# mplex_v2.net
KiCad netlist of a schematic drawn in EAGLE
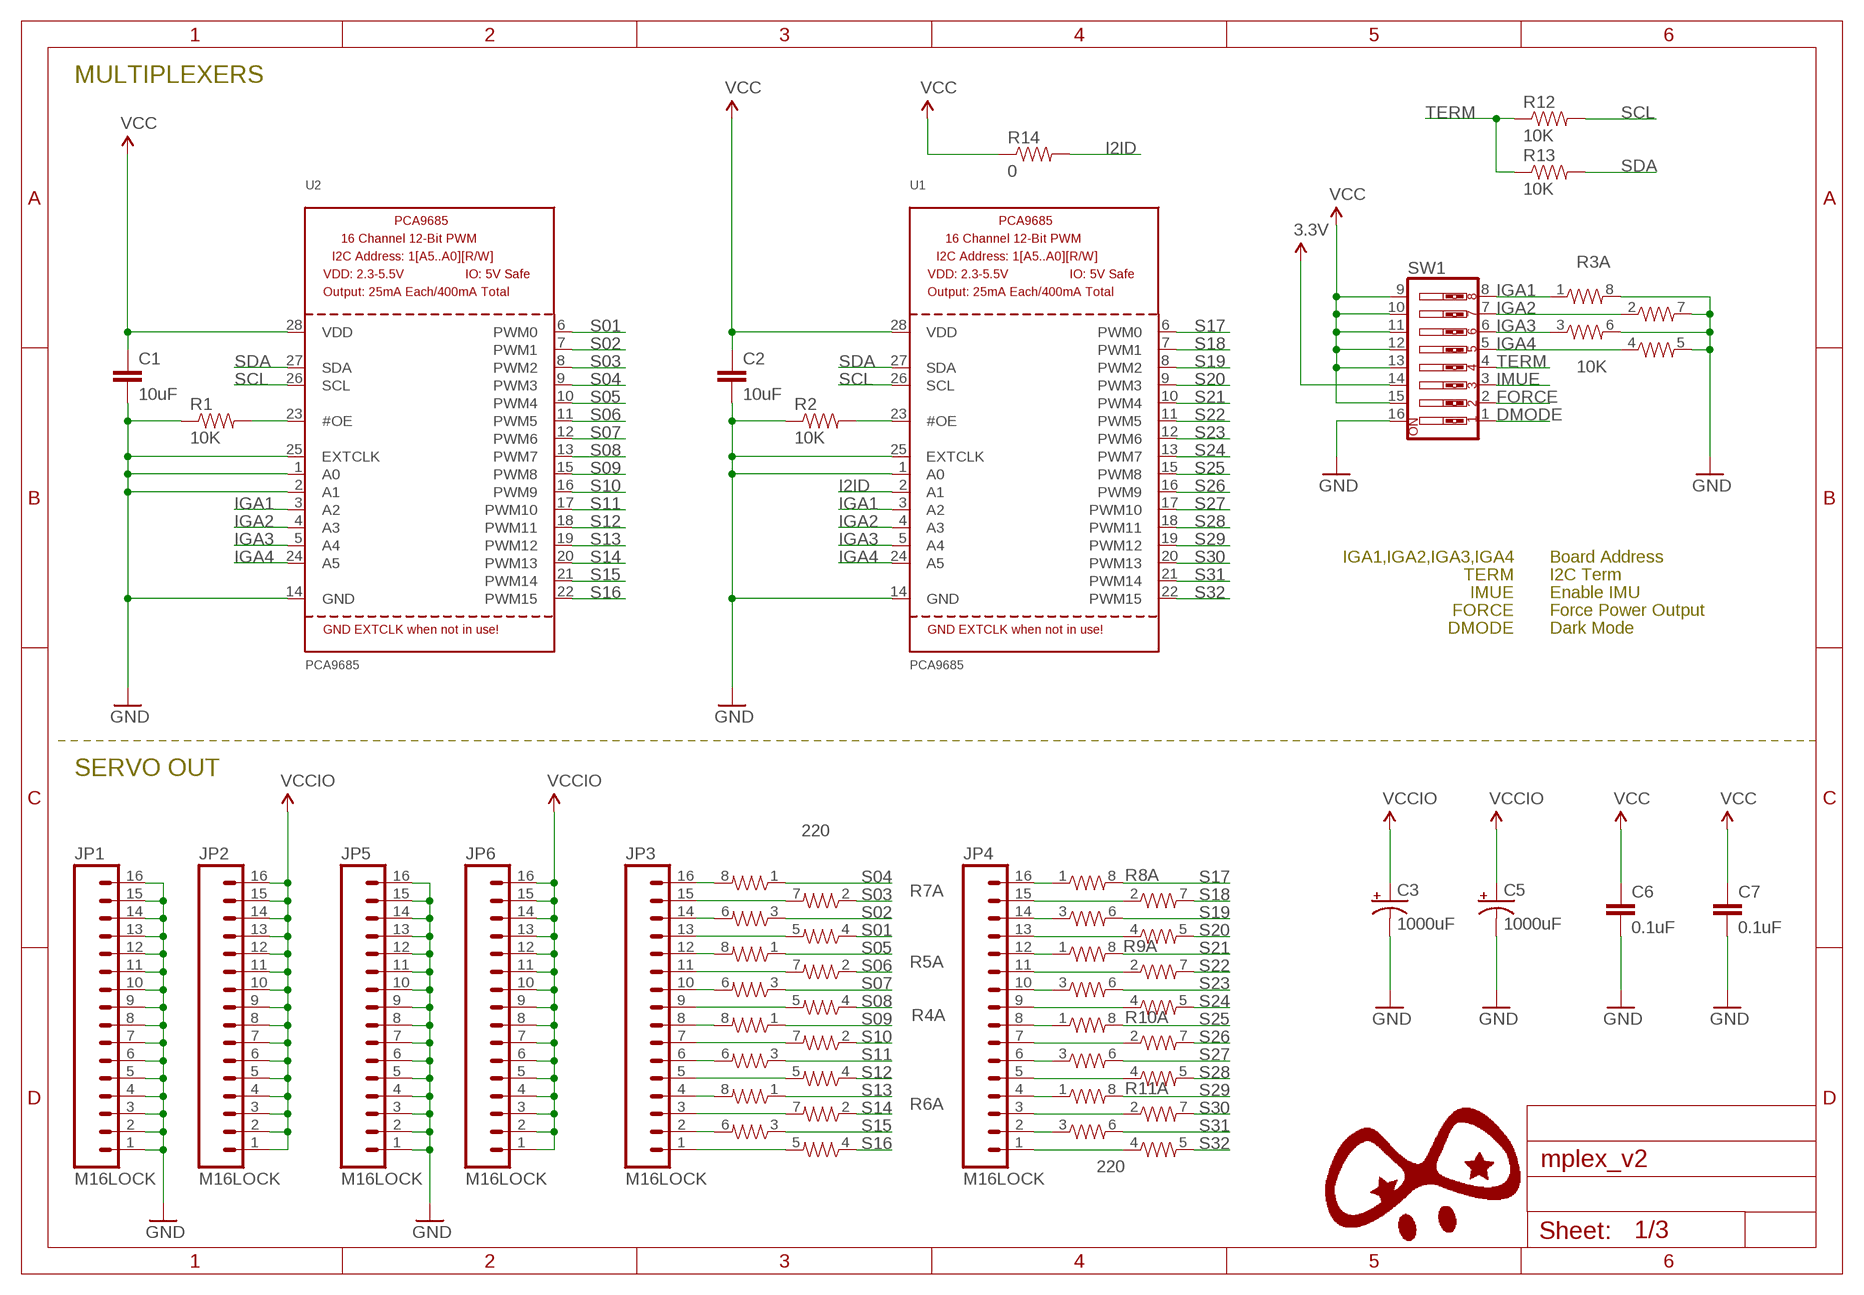
[diagram p0: schematic, sheet 1]
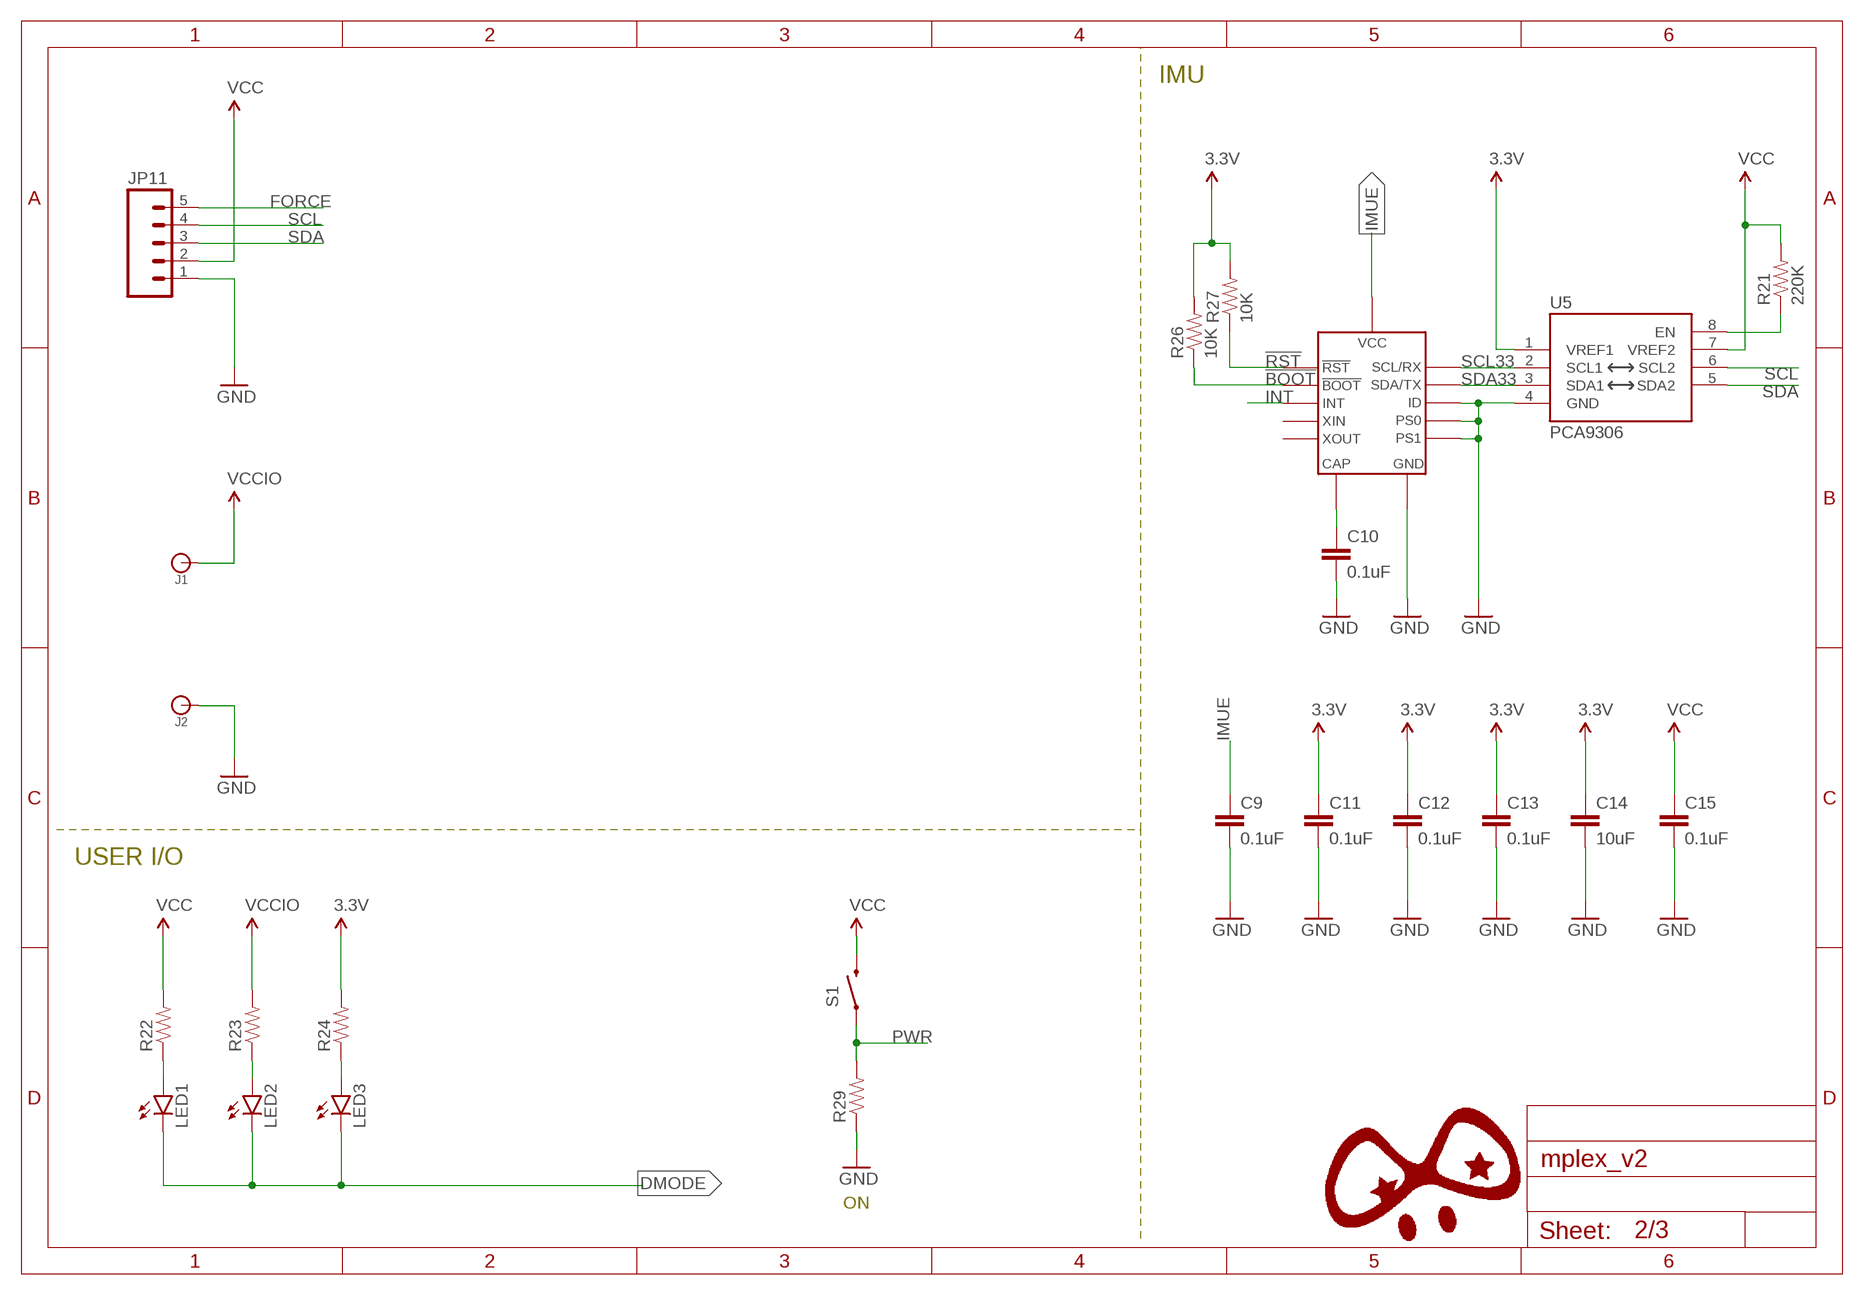
[diagram p1: schematic, sheet 2]
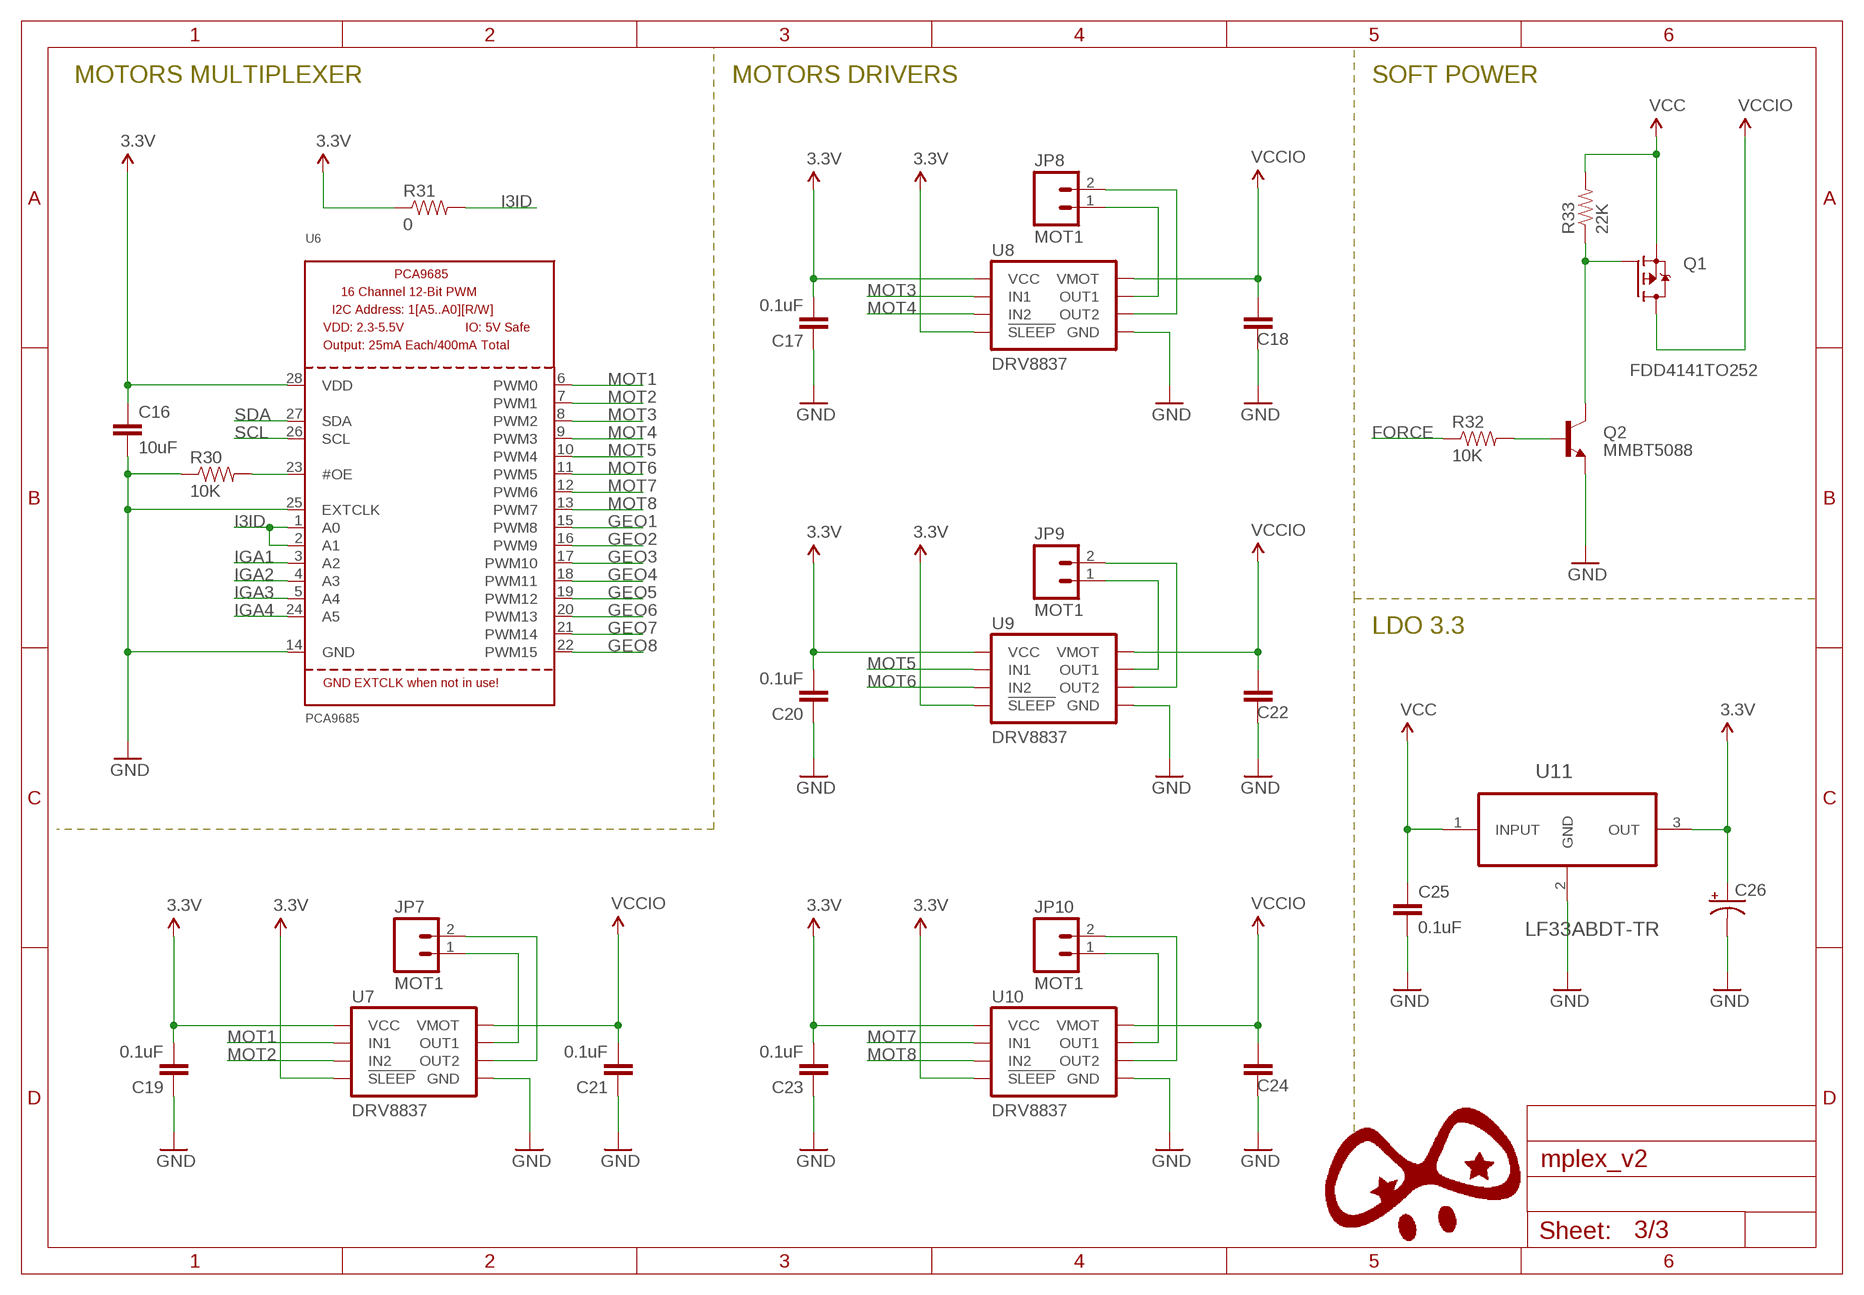
[diagram p2: schematic, sheet 3]

(export (version "E")
  (design (tool "Eeschema 10.0.6"))
  (components
    (comp (ref "C16")
      (value "10uF")
      (footprint "eagle-import:0603-CAP")
      (libsource (lib "eagle-import") (part "10UF-6.3V-20%(0603)"))
    )
    (comp (ref "C17")
      (value "0.1uF")
      (footprint "eagle-import:0603-CAP")
      (libsource (lib "eagle-import") (part "SparkFun-Passives_CAP0603-CAP"))
    )
    (comp (ref "C18")
      (value "0.1uF")
      (footprint "eagle-import:0603-CAP")
      (libsource (lib "eagle-import") (part "SparkFun-Passives_CAP0603-CAP"))
    )
    (comp (ref "C19")
      (value "0.1uF")
      (footprint "eagle-import:0603-CAP")
      (libsource (lib "eagle-import") (part "SparkFun-Passives_CAP0603-CAP"))
    )
    (comp (ref "C20")
      (value "0.1uF")
      (footprint "eagle-import:0603-CAP")
      (libsource (lib "eagle-import") (part "SparkFun-Passives_CAP0603-CAP"))
    )
    (comp (ref "C21")
      (value "0.1uF")
      (footprint "eagle-import:0603-CAP")
      (libsource (lib "eagle-import") (part "SparkFun-Passives_CAP0603-CAP"))
    )
    (comp (ref "C22")
      (value "0.1uF")
      (footprint "eagle-import:0603-CAP")
      (libsource (lib "eagle-import") (part "SparkFun-Passives_CAP0603-CAP"))
    )
    (comp (ref "C23")
      (value "0.1uF")
      (footprint "eagle-import:0603-CAP")
      (libsource (lib "eagle-import") (part "SparkFun-Passives_CAP0603-CAP"))
    )
    (comp (ref "C24")
      (value "0.1uF")
      (footprint "eagle-import:0603-CAP")
      (libsource (lib "eagle-import") (part "SparkFun-Passives_CAP0603-CAP"))
    )
    (comp (ref "C25")
      (value "0.1uF")
      (footprint "eagle-import:1210")
      (libsource (lib "eagle-import") (part "CAP1210"))
    )
    (comp (ref "C26")
      (value "CAP_POLD")
      (footprint "eagle-import:PANASONIC_D")
      (libsource (lib "eagle-import") (part "CAP_POLD"))
    )
    (comp (ref "JP7")
      (value "MOT1")
      (footprint "eagle-import:MOLEX-1X2")
      (libsource (lib "eagle-import") (part "M02POLAR"))
    )
    (comp (ref "JP8")
      (value "MOT1")
      (footprint "eagle-import:MOLEX-1X2")
      (libsource (lib "eagle-import") (part "M02POLAR"))
    )
    (comp (ref "JP9")
      (value "MOT1")
      (footprint "eagle-import:MOLEX-1X2")
      (libsource (lib "eagle-import") (part "M02POLAR"))
    )
    (comp (ref "JP10")
      (value "MOT1")
      (footprint "eagle-import:MOLEX-1X2")
      (libsource (lib "eagle-import") (part "M02POLAR"))
    )
    (comp (ref "Q1")
      (value "FDD4141TO252")
      (footprint "eagle-import:TO252")
      (libsource (lib "eagle-import") (part "FDD4141TO252"))
    )
    (comp (ref "Q2")
      (value "MMBT5088")
      (footprint "eagle-import:SOT23-3")
      (libsource (lib "eagle-import") (part "TRANSISTOR_NPNMMBT5088"))
    )
    (comp (ref "R30")
      (value "10K")
      (footprint "eagle-import:0603-RES")
      (libsource (lib "eagle-import") (part "RESISTOR0603"))
    )
    (comp (ref "R31")
      (value "0")
      (footprint "eagle-import:0603-RES")
      (libsource (lib "eagle-import") (part "RESISTOR0603"))
    )
    (comp (ref "R32")
      (value "10K")
      (footprint "eagle-import:0603-RES")
      (libsource (lib "eagle-import") (part "RESISTOR0603"))
    )
    (comp (ref "R33")
      (value "22K")
      (footprint "eagle-import:0603-RES")
      (libsource (lib "eagle-import") (part "RESISTOR0603"))
    )
    (comp (ref "U6")
      (value "PCA9685")
      (footprint "eagle-import:TSSOP28")
      (libsource (lib "eagle-import") (part "PCA9685"))
    )
    (comp (ref "U7")
      (value "DRV8837")
      (footprint "eagle-import:DSG")
      (libsource (lib "eagle-import") (part "DRV8837"))
    )
    (comp (ref "U8")
      (value "DRV8837")
      (footprint "eagle-import:DSG")
      (libsource (lib "eagle-import") (part "DRV8837"))
    )
    (comp (ref "U9")
      (value "DRV8837")
      (footprint "eagle-import:DSG")
      (libsource (lib "eagle-import") (part "DRV8837"))
    )
    (comp (ref "U10")
      (value "DRV8837")
      (footprint "eagle-import:DSG")
      (libsource (lib "eagle-import") (part "DRV8837"))
    )
    (comp (ref "U11")
      (value "LF33ABDT-TR")
      (footprint "eagle-import:TO228P972X240-3N")
      (libsource (lib "eagle-import") (part "LF33ABDT-TR"))
    )
    (comp (ref "C9")
      (value "0.1uF")
      (footprint "eagle-import:0603-CAP")
      (libsource (lib "eagle-import") (part "10UF-6.3V-20%(0603)"))
    )
    (comp (ref "C10")
      (value "0.1uF")
      (footprint "eagle-import:0603-CAP")
      (libsource (lib "eagle-import") (part "10UF-6.3V-20%(0603)"))
    )
    (comp (ref "C11")
      (value "0.1uF")
      (footprint "eagle-import:0603-CAP")
      (libsource (lib "eagle-import") (part "10UF-6.3V-20%(0603)"))
    )
    (comp (ref "C12")
      (value "0.1uF")
      (footprint "eagle-import:0603-CAP")
      (libsource (lib "eagle-import") (part "10UF-6.3V-20%(0603)"))
    )
    (comp (ref "C13")
      (value "0.1uF")
      (footprint "eagle-import:0603-CAP")
      (libsource (lib "eagle-import") (part "10UF-6.3V-20%(0603)"))
    )
    (comp (ref "C14")
      (value "10uF")
      (footprint "eagle-import:0603-CAP")
      (libsource (lib "eagle-import") (part "10UF-6.3V-20%(0603)"))
    )
    (comp (ref "C15")
      (value "0.1uF")
      (footprint "eagle-import:0603-CAP")
      (libsource (lib "eagle-import") (part "10UF-6.3V-20%(0603)"))
    )
    (comp (ref "J1")
      (value "BANANA_CONN")
      (footprint "eagle-import:BANANA_CONN")
      (libsource (lib "eagle-import") (part "BANANA_CONN"))
    )
    (comp (ref "J2")
      (value "BANANA_CONN")
      (footprint "eagle-import:BANANA_CONN")
      (libsource (lib "eagle-import") (part "BANANA_CONN"))
    )
    (comp (ref "JP11")
      (value "M05LOCK")
      (footprint "eagle-import:1X05_LOCK")
      (libsource (lib "eagle-import") (part "M05LOCK"))
    )
    (comp (ref "LED1")
      (value "LED0603")
      (footprint "eagle-import:LED-0603")
      (libsource (lib "eagle-import") (part "LED0603"))
    )
    (comp (ref "LED2")
      (value "LED0603")
      (footprint "eagle-import:LED-0603")
      (libsource (lib "eagle-import") (part "LED0603"))
    )
    (comp (ref "LED3")
      (value "LED0603")
      (footprint "eagle-import:LED-0603")
      (libsource (lib "eagle-import") (part "LED0603"))
    )
    (comp (ref "R21")
      (value "220K")
      (footprint "eagle-import:0603-RES")
      (libsource (lib "eagle-import") (part "RESISTOR0603-RES"))
    )
    (comp (ref "R22")
      (value "RESISTOR0603-RES")
      (footprint "eagle-import:0603-RES")
      (libsource (lib "eagle-import") (part "RESISTOR0603-RES"))
    )
    (comp (ref "R23")
      (value "RESISTOR0603-RES")
      (footprint "eagle-import:0603-RES")
      (libsource (lib "eagle-import") (part "RESISTOR0603-RES"))
    )
    (comp (ref "R24")
      (value "RESISTOR0603-RES")
      (footprint "eagle-import:0603-RES")
      (libsource (lib "eagle-import") (part "RESISTOR0603-RES"))
    )
    (comp (ref "R26")
      (value "10K")
      (footprint "eagle-import:0603-RES")
      (libsource (lib "eagle-import") (part "RESISTOR0603"))
    )
    (comp (ref "R27")
      (value "10K")
      (footprint "eagle-import:0603-RES")
      (libsource (lib "eagle-import") (part "RESISTOR0603"))
    )
    (comp (ref "R29")
      (value "RESISTOR0603-RES")
      (footprint "eagle-import:0603-RES")
      (libsource (lib "eagle-import") (part "RESISTOR0603-RES"))
    )
    (comp (ref "S1")
      (value "SWITCH-MOMENTARY-2SMD")
      (footprint "eagle-import:TACTILE-SWITCH-SMD")
      (libsource (lib "eagle-import") (part "SWITCH-MOMENTARY-2SMD"))
    )
    (comp (ref "U4")
      (value "BNO055")
      (footprint "eagle-import:BNO055")
      (libsource (lib "eagle-import") (part "BNO055"))
    )
    (comp (ref "U5")
      (value "PCA9306")
      (footprint "eagle-import:PCA9306DC-1_1")
      (libsource (lib "eagle-import") (part "PCA9306PCA9306DC-1{colon}1"))
    )
    (comp (ref "C1")
      (value "10uF")
      (footprint "eagle-import:0603-CAP")
      (libsource (lib "eagle-import") (part "10UF-6.3V-20%(0603)"))
    )
    (comp (ref "C2")
      (value "10uF")
      (footprint "eagle-import:0603-CAP")
      (libsource (lib "eagle-import") (part "10UF-6.3V-20%(0603)"))
    )
    (comp (ref "C3")
      (value "1000uF")
      (footprint "eagle-import:PANASONIC_D")
      (libsource (lib "eagle-import") (part "CAP_POLD"))
    )
    (comp (ref "C5")
      (value "1000uF")
      (footprint "eagle-import:PANASONIC_D")
      (libsource (lib "eagle-import") (part "CAP_POLD"))
    )
    (comp (ref "C6")
      (value "0.1uF")
      (footprint "eagle-import:0603-CAP")
      (libsource (lib "eagle-import") (part "10UF-6.3V-20%(0603)"))
    )
    (comp (ref "C7")
      (value "0.1uF")
      (footprint "eagle-import:0603-CAP")
      (libsource (lib "eagle-import") (part "10UF-6.3V-20%(0603)"))
    )
    (comp (ref "JP1")
      (value "M16LOCK")
      (footprint "eagle-import:1X16_LOCK")
      (libsource (lib "eagle-import") (part "M16LOCK"))
    )
    (comp (ref "JP2")
      (value "M16LOCK")
      (footprint "eagle-import:1X16_LOCK")
      (libsource (lib "eagle-import") (part "M16LOCK"))
    )
    (comp (ref "JP3")
      (value "M16LOCK")
      (footprint "eagle-import:1X16_LOCK")
      (libsource (lib "eagle-import") (part "M16LOCK"))
    )
    (comp (ref "JP4")
      (value "M16LOCK")
      (footprint "eagle-import:1X16_LOCK")
      (libsource (lib "eagle-import") (part "M16LOCK"))
    )
    (comp (ref "JP5")
      (value "M16LOCK")
      (footprint "eagle-import:1X16_LOCK")
      (libsource (lib "eagle-import") (part "M16LOCK"))
    )
    (comp (ref "JP6")
      (value "M16LOCK")
      (footprint "eagle-import:1X16_LOCK")
      (libsource (lib "eagle-import") (part "M16LOCK"))
    )
    (comp (ref "R1")
      (value "10K")
      (footprint "eagle-import:0603-RES")
      (libsource (lib "eagle-import") (part "RESISTOR0603"))
    )
    (comp (ref "R2")
      (value "10K")
      (footprint "eagle-import:0603-RES")
      (libsource (lib "eagle-import") (part "RESISTOR0603"))
    )
    (comp (ref "R3")
      (value "10K")
      (footprint "eagle-import:0603-ARV")
      (libsource (lib "eagle-import") (part "RESISTOR-ARRAY0603-ARV"))
    )
    (comp (ref "R4")
      (value "220")
      (footprint "eagle-import:0603-ARV")
      (libsource (lib "eagle-import") (part "RESISTOR-ARRAY0603-ARV"))
    )
    (comp (ref "R5")
      (value "220")
      (footprint "eagle-import:0603-ARV")
      (libsource (lib "eagle-import") (part "RESISTOR-ARRAY0603-ARV"))
    )
    (comp (ref "R6")
      (value "220")
      (footprint "eagle-import:0603-ARV")
      (libsource (lib "eagle-import") (part "RESISTOR-ARRAY0603-ARV"))
    )
    (comp (ref "R7")
      (value "220")
      (footprint "eagle-import:0603-ARV")
      (libsource (lib "eagle-import") (part "RESISTOR-ARRAY0603-ARV"))
    )
    (comp (ref "R8")
      (value "220")
      (footprint "eagle-import:0603-ARV")
      (libsource (lib "eagle-import") (part "RESISTOR-ARRAY0603-ARV"))
    )
    (comp (ref "R9")
      (value "220")
      (footprint "eagle-import:0603-ARV")
      (libsource (lib "eagle-import") (part "RESISTOR-ARRAY0603-ARV"))
    )
    (comp (ref "R10")
      (value "220")
      (footprint "eagle-import:0603-ARV")
      (libsource (lib "eagle-import") (part "RESISTOR-ARRAY0603-ARV"))
    )
    (comp (ref "R11")
      (value "220")
      (footprint "eagle-import:0603-ARV")
      (libsource (lib "eagle-import") (part "RESISTOR-ARRAY0603-ARV"))
    )
    (comp (ref "R12")
      (value "10K")
      (footprint "eagle-import:0603-RES")
      (libsource (lib "eagle-import") (part "RESISTOR0603"))
    )
    (comp (ref "R13")
      (value "10K")
      (footprint "eagle-import:0603-RES")
      (libsource (lib "eagle-import") (part "RESISTOR0603"))
    )
    (comp (ref "R14")
      (value "0")
      (footprint "eagle-import:0603-RES")
      (libsource (lib "eagle-import") (part "RESISTOR0603"))
    )
    (comp (ref "SW1")
      (value "SW_DIP-8-SMT-HALFSIZE")
      (footprint "eagle-import:DIPSWITCH-08-50MIL")
      (libsource (lib "eagle-import") (part "SW_DIP-8-SMT-HALFSIZE"))
    )
    (comp (ref "U1")
      (value "PCA9685")
      (footprint "eagle-import:TSSOP28")
      (libsource (lib "eagle-import") (part "PCA9685"))
    )
    (comp (ref "U2")
      (value "PCA9685")
      (footprint "eagle-import:TSSOP28")
      (libsource (lib "eagle-import") (part "PCA9685"))
    )
  )
  (nets
    (net (code "1") (name "3.3V") (class "Default")
      (node (ref "C11") (pin "1") (pinfunction "1_1") (pintype "passive"))
      (node (ref "C12") (pin "1") (pinfunction "1_1") (pintype "passive"))
      (node (ref "C13") (pin "1") (pinfunction "1_1") (pintype "passive"))
      (node (ref "C14") (pin "1") (pinfunction "1_1") (pintype "passive"))
      (node (ref "C16") (pin "1") (pinfunction "1_1") (pintype "passive"))
      (node (ref "C17") (pin "2") (pinfunction "2_2") (pintype "passive"))
      (node (ref "C19") (pin "2") (pinfunction "2_2") (pintype "passive"))
      (node (ref "C20") (pin "2") (pinfunction "2_2") (pintype "passive"))
      (node (ref "C23") (pin "2") (pinfunction "2_2") (pintype "passive"))
      (node (ref "C26") (pin "+") (pinfunction "+_+") (pintype "passive"))
      (node (ref "R24") (pin "2") (pinfunction "2_2") (pintype "passive"))
      (node (ref "R26") (pin "2") (pinfunction "2_2") (pintype "passive"))
      (node (ref "R27") (pin "2") (pinfunction "2_2") (pintype "passive"))
      (node (ref "R31") (pin "1") (pinfunction "1_1") (pintype "passive"))
      (node (ref "SW1") (pin "14") (pinfunction "14_14") (pintype "passive"))
      (node (ref "U10") (pin "7") (pinfunction "~{SLEEP}_7") (pintype "bidirectional"))
      (node (ref "U10") (pin "8") (pinfunction "VCC_8") (pintype "bidirectional"))
      (node (ref "U11") (pin "3") (pinfunction "OUT_3") (pintype "output"))
      (node (ref "U5") (pin "1") (pinfunction "VREF1_1") (pintype "bidirectional"))
      (node (ref "U6") (pin "28") (pinfunction "VDD_28") (pintype "power_in"))
      (node (ref "U7") (pin "7") (pinfunction "~{SLEEP}_7") (pintype "bidirectional"))
      (node (ref "U7") (pin "8") (pinfunction "VCC_8") (pintype "bidirectional"))
      (node (ref "U8") (pin "7") (pinfunction "~{SLEEP}_7") (pintype "bidirectional"))
      (node (ref "U8") (pin "8") (pinfunction "VCC_8") (pintype "bidirectional"))
      (node (ref "U9") (pin "7") (pinfunction "~{SLEEP}_7") (pintype "bidirectional"))
      (node (ref "U9") (pin "8") (pinfunction "VCC_8") (pintype "bidirectional"))
    )
    (net (code "2") (name "DMODE") (class "Default")
      (node (ref "LED1") (pin "C") (pinfunction "C_C") (pintype "passive"))
      (node (ref "LED2") (pin "C") (pinfunction "C_C") (pintype "passive"))
      (node (ref "LED3") (pin "C") (pinfunction "C_C") (pintype "passive"))
      (node (ref "SW1") (pin "1") (pinfunction "1_1") (pintype "passive"))
    )
    (net (code "3") (name "FORCE") (class "Default")
      (node (ref "JP11") (pin "5") (pinfunction "5_5") (pintype "passive"))
      (node (ref "R32") (pin "1") (pinfunction "1_1") (pintype "passive"))
      (node (ref "SW1") (pin "2") (pinfunction "2_2") (pintype "passive"))
    )
    (net (code "4") (name "GEO1") (class "Default")
      (node (ref "U6") (pin "15") (pinfunction "PWM8_15") (pintype "output"))
    )
    (net (code "5") (name "GEO2") (class "Default")
      (node (ref "U6") (pin "16") (pinfunction "PWM9_16") (pintype "output"))
    )
    (net (code "6") (name "GEO3") (class "Default")
      (node (ref "U6") (pin "17") (pinfunction "PWM10_17") (pintype "output"))
    )
    (net (code "7") (name "GEO4") (class "Default")
      (node (ref "U6") (pin "18") (pinfunction "PWM11_18") (pintype "output"))
    )
    (net (code "8") (name "GEO5") (class "Default")
      (node (ref "U6") (pin "19") (pinfunction "PWM12_19") (pintype "output"))
    )
    (net (code "9") (name "GEO6") (class "Default")
      (node (ref "U6") (pin "20") (pinfunction "PWM13_20") (pintype "output"))
    )
    (net (code "10") (name "GEO7") (class "Default")
      (node (ref "U6") (pin "21") (pinfunction "PWM14_21") (pintype "output"))
    )
    (net (code "11") (name "GEO8") (class "Default")
      (node (ref "U6") (pin "22") (pinfunction "PWM15_22") (pintype "output"))
    )
    (net (code "12") (name "GND") (class "Default")
      (node (ref "C1") (pin "2") (pinfunction "2_2") (pintype "passive"))
      (node (ref "C10") (pin "2") (pinfunction "2_2") (pintype "passive"))
      (node (ref "C11") (pin "2") (pinfunction "2_2") (pintype "passive"))
      (node (ref "C12") (pin "2") (pinfunction "2_2") (pintype "passive"))
      (node (ref "C13") (pin "2") (pinfunction "2_2") (pintype "passive"))
      (node (ref "C14") (pin "2") (pinfunction "2_2") (pintype "passive"))
      (node (ref "C15") (pin "2") (pinfunction "2_2") (pintype "passive"))
      (node (ref "C16") (pin "2") (pinfunction "2_2") (pintype "passive"))
      (node (ref "C17") (pin "1") (pinfunction "1_1") (pintype "passive"))
      (node (ref "C18") (pin "1") (pinfunction "1_1") (pintype "passive"))
      (node (ref "C19") (pin "1") (pinfunction "1_1") (pintype "passive"))
      (node (ref "C2") (pin "2") (pinfunction "2_2") (pintype "passive"))
      (node (ref "C20") (pin "1") (pinfunction "1_1") (pintype "passive"))
      (node (ref "C21") (pin "1") (pinfunction "1_1") (pintype "passive"))
      (node (ref "C22") (pin "1") (pinfunction "1_1") (pintype "passive"))
      (node (ref "C23") (pin "1") (pinfunction "1_1") (pintype "passive"))
      (node (ref "C24") (pin "1") (pinfunction "1_1") (pintype "passive"))
      (node (ref "C25") (pin "2") (pinfunction "2_2") (pintype "passive"))
      (node (ref "C26") (pin "-") (pinfunction "-_-") (pintype "passive"))
      (node (ref "C3") (pin "-") (pinfunction "-_-") (pintype "passive"))
      (node (ref "C5") (pin "-") (pinfunction "-_-") (pintype "passive"))
      (node (ref "C6") (pin "2") (pinfunction "2_2") (pintype "passive"))
      (node (ref "C7") (pin "2") (pinfunction "2_2") (pintype "passive"))
      (node (ref "C9") (pin "2") (pinfunction "2_2") (pintype "passive"))
      (node (ref "J2") (pin "P$1") (pinfunction "1_P$1") (pintype "passive"))
      (node (ref "JP1") (pin "1") (pinfunction "1_1") (pintype "passive"))
      (node (ref "JP1") (pin "10") (pinfunction "10_10") (pintype "passive"))
      (node (ref "JP1") (pin "11") (pinfunction "11_11") (pintype "passive"))
      (node (ref "JP1") (pin "12") (pinfunction "12_12") (pintype "passive"))
      (node (ref "JP1") (pin "13") (pinfunction "13_13") (pintype "passive"))
      (node (ref "JP1") (pin "14") (pinfunction "14_14") (pintype "passive"))
      (node (ref "JP1") (pin "15") (pinfunction "15_15") (pintype "passive"))
      (node (ref "JP1") (pin "16") (pinfunction "16_16") (pintype "passive"))
      (node (ref "JP1") (pin "2") (pinfunction "2_2") (pintype "passive"))
      (node (ref "JP1") (pin "3") (pinfunction "3_3") (pintype "passive"))
      (node (ref "JP1") (pin "4") (pinfunction "4_4") (pintype "passive"))
      (node (ref "JP1") (pin "5") (pinfunction "5_5") (pintype "passive"))
      (node (ref "JP1") (pin "6") (pinfunction "6_6") (pintype "passive"))
      (node (ref "JP1") (pin "7") (pinfunction "7_7") (pintype "passive"))
      (node (ref "JP1") (pin "8") (pinfunction "8_8") (pintype "passive"))
      (node (ref "JP1") (pin "9") (pinfunction "9_9") (pintype "passive"))
      (node (ref "JP11") (pin "1") (pinfunction "1_1") (pintype "passive"))
      (node (ref "JP5") (pin "1") (pinfunction "1_1") (pintype "passive"))
      (node (ref "JP5") (pin "10") (pinfunction "10_10") (pintype "passive"))
      (node (ref "JP5") (pin "11") (pinfunction "11_11") (pintype "passive"))
      (node (ref "JP5") (pin "12") (pinfunction "12_12") (pintype "passive"))
      (node (ref "JP5") (pin "13") (pinfunction "13_13") (pintype "passive"))
      (node (ref "JP5") (pin "14") (pinfunction "14_14") (pintype "passive"))
      (node (ref "JP5") (pin "15") (pinfunction "15_15") (pintype "passive"))
      (node (ref "JP5") (pin "16") (pinfunction "16_16") (pintype "passive"))
      (node (ref "JP5") (pin "2") (pinfunction "2_2") (pintype "passive"))
      (node (ref "JP5") (pin "3") (pinfunction "3_3") (pintype "passive"))
      (node (ref "JP5") (pin "4") (pinfunction "4_4") (pintype "passive"))
      (node (ref "JP5") (pin "5") (pinfunction "5_5") (pintype "passive"))
      (node (ref "JP5") (pin "6") (pinfunction "6_6") (pintype "passive"))
      (node (ref "JP5") (pin "7") (pinfunction "7_7") (pintype "passive"))
      (node (ref "JP5") (pin "8") (pinfunction "8_8") (pintype "passive"))
      (node (ref "JP5") (pin "9") (pinfunction "9_9") (pintype "passive"))
      (node (ref "Q2") (pin "2") (pinfunction "E_2") (pintype "passive"))
      (node (ref "R1") (pin "1") (pinfunction "1_1") (pintype "passive"))
      (node (ref "R2") (pin "1") (pinfunction "1_1") (pintype "passive"))
      (node (ref "R29") (pin "1") (pinfunction "1_1") (pintype "passive"))
      (node (ref "R3") (pin "5") (pinfunction "2_5") (pintype "passive"))
      (node (ref "R3") (pin "6") (pinfunction "2_6") (pintype "passive"))
      (node (ref "R3") (pin "7") (pinfunction "2_7") (pintype "passive"))
      (node (ref "R3") (pin "8") (pinfunction "2_8") (pintype "passive"))
      (node (ref "R30") (pin "1") (pinfunction "1_1") (pintype "passive"))
      (node (ref "SW1") (pin "16") (pinfunction "16_16") (pintype "passive"))
      (node (ref "U1") (pin "1") (pinfunction "A0_1") (pintype "bidirectional"))
      (node (ref "U1") (pin "14") (pinfunction "GND_14") (pintype "power_in"))
      (node (ref "U1") (pin "25") (pinfunction "EXTCLK_25") (pintype "input"))
      (node (ref "U10") (pin "4") (pinfunction "GND_4") (pintype "bidirectional"))
      (node (ref "U10") (pin "PAD") (pinfunction "GND_PAD") (pintype "bidirectional"))
      (node (ref "U11") (pin "2") (pinfunction "GND_2") (pintype "passive"))
      (node (ref "U2") (pin "1") (pinfunction "A0_1") (pintype "bidirectional"))
      (node (ref "U2") (pin "14") (pinfunction "GND_14") (pintype "power_in"))
      (node (ref "U2") (pin "2") (pinfunction "A1_2") (pintype "bidirectional"))
      (node (ref "U2") (pin "25") (pinfunction "EXTCLK_25") (pintype "input"))
      (node (ref "U4") (pin "10") (pinfunction "GND_10") (pintype "power_in"))
      (node (ref "U4") (pin "15") (pinfunction "GND_15") (pintype "power_in"))
      (node (ref "U4") (pin "16") (pinfunction "GND_16") (pintype "power_in"))
      (node (ref "U4") (pin "17") (pinfunction "ID_17") (pintype "bidirectional"))
      (node (ref "U4") (pin "18") (pinfunction "GND_18") (pintype "power_in"))
      (node (ref "U4") (pin "2") (pinfunction "GND_2") (pintype "power_in"))
      (node (ref "U4") (pin "25") (pinfunction "GND_25") (pintype "power_in"))
      (node (ref "U4") (pin "5") (pinfunction "PS1_5") (pintype "bidirectional"))
      (node (ref "U4") (pin "6") (pinfunction "PS0_6") (pintype "bidirectional"))
      (node (ref "U5") (pin "4") (pinfunction "GND_4") (pintype "bidirectional"))
      (node (ref "U6") (pin "14") (pinfunction "GND_14") (pintype "power_in"))
      (node (ref "U6") (pin "25") (pinfunction "EXTCLK_25") (pintype "input"))
      (node (ref "U7") (pin "4") (pinfunction "GND_4") (pintype "bidirectional"))
      (node (ref "U7") (pin "PAD") (pinfunction "GND_PAD") (pintype "bidirectional"))
      (node (ref "U8") (pin "4") (pinfunction "GND_4") (pintype "bidirectional"))
      (node (ref "U8") (pin "PAD") (pinfunction "GND_PAD") (pintype "bidirectional"))
      (node (ref "U9") (pin "4") (pinfunction "GND_4") (pintype "bidirectional"))
      (node (ref "U9") (pin "PAD") (pinfunction "GND_PAD") (pintype "bidirectional"))
    )
    (net (code "13") (name "I2ID") (class "Default")
      (node (ref "R14") (pin "2") (pinfunction "2_2") (pintype "passive"))
      (node (ref "U1") (pin "2") (pinfunction "A1_2") (pintype "bidirectional"))
    )
    (net (code "14") (name "I3ID") (class "Default")
      (node (ref "R31") (pin "2") (pinfunction "2_2") (pintype "passive"))
      (node (ref "U6") (pin "1") (pinfunction "A0_1") (pintype "bidirectional"))
      (node (ref "U6") (pin "2") (pinfunction "A1_2") (pintype "bidirectional"))
    )
    (net (code "15") (name "IGA1") (class "Default")
      (node (ref "R3") (pin "1") (pinfunction "1_1") (pintype "passive"))
      (node (ref "SW1") (pin "8") (pinfunction "8_8") (pintype "passive"))
      (node (ref "U1") (pin "3") (pinfunction "A2_3") (pintype "bidirectional"))
      (node (ref "U2") (pin "3") (pinfunction "A2_3") (pintype "bidirectional"))
      (node (ref "U6") (pin "3") (pinfunction "A2_3") (pintype "bidirectional"))
    )
    (net (code "16") (name "IGA2") (class "Default")
      (node (ref "R3") (pin "2") (pinfunction "1_2") (pintype "passive"))
      (node (ref "SW1") (pin "7") (pinfunction "7_7") (pintype "passive"))
      (node (ref "U1") (pin "4") (pinfunction "A3_4") (pintype "bidirectional"))
      (node (ref "U2") (pin "4") (pinfunction "A3_4") (pintype "bidirectional"))
      (node (ref "U6") (pin "4") (pinfunction "A3_4") (pintype "bidirectional"))
    )
    (net (code "17") (name "IGA3") (class "Default")
      (node (ref "R3") (pin "3") (pinfunction "1_3") (pintype "passive"))
      (node (ref "SW1") (pin "6") (pinfunction "6_6") (pintype "passive"))
      (node (ref "U1") (pin "5") (pinfunction "A4_5") (pintype "bidirectional"))
      (node (ref "U2") (pin "5") (pinfunction "A4_5") (pintype "bidirectional"))
      (node (ref "U6") (pin "5") (pinfunction "A4_5") (pintype "bidirectional"))
    )
    (net (code "18") (name "IGA4") (class "Default")
      (node (ref "R3") (pin "4") (pinfunction "1_4") (pintype "passive"))
      (node (ref "SW1") (pin "5") (pinfunction "5_5") (pintype "passive"))
      (node (ref "U1") (pin "24") (pinfunction "A5_24") (pintype "bidirectional"))
      (node (ref "U2") (pin "24") (pinfunction "A5_24") (pintype "bidirectional"))
      (node (ref "U6") (pin "24") (pinfunction "A5_24") (pintype "bidirectional"))
    )
    (net (code "19") (name "IMUE") (class "Default")
      (node (ref "C9") (pin "1") (pinfunction "1_1") (pintype "passive"))
      (node (ref "SW1") (pin "3") (pinfunction "3_3") (pintype "passive"))
      (node (ref "U4") (pin "28") (pinfunction "VCC_28") (pintype "bidirectional"))
      (node (ref "U4") (pin "3") (pinfunction "VCC_3") (pintype "bidirectional"))
    )
    (net (code "20") (name "INT") (class "Default")
      (node (ref "U4") (pin "14") (pinfunction "INT_14") (pintype "bidirectional"))
    )
    (net (code "21") (name "MOT1") (class "Default")
      (node (ref "U6") (pin "6") (pinfunction "PWM0_6") (pintype "output"))
      (node (ref "U7") (pin "6") (pinfunction "IN1_6") (pintype "bidirectional"))
    )
    (net (code "22") (name "MOT2") (class "Default")
      (node (ref "U6") (pin "7") (pinfunction "PWM1_7") (pintype "output"))
      (node (ref "U7") (pin "5") (pinfunction "IN2_5") (pintype "bidirectional"))
    )
    (net (code "23") (name "MOT3") (class "Default")
      (node (ref "U6") (pin "8") (pinfunction "PWM2_8") (pintype "output"))
      (node (ref "U8") (pin "6") (pinfunction "IN1_6") (pintype "bidirectional"))
    )
    (net (code "24") (name "MOT4") (class "Default")
      (node (ref "U6") (pin "9") (pinfunction "PWM3_9") (pintype "output"))
      (node (ref "U8") (pin "5") (pinfunction "IN2_5") (pintype "bidirectional"))
    )
    (net (code "25") (name "MOT5") (class "Default")
      (node (ref "U6") (pin "10") (pinfunction "PWM4_10") (pintype "output"))
      (node (ref "U9") (pin "6") (pinfunction "IN1_6") (pintype "bidirectional"))
    )
    (net (code "26") (name "MOT6") (class "Default")
      (node (ref "U6") (pin "11") (pinfunction "PWM5_11") (pintype "output"))
      (node (ref "U9") (pin "5") (pinfunction "IN2_5") (pintype "bidirectional"))
    )
    (net (code "27") (name "MOT7") (class "Default")
      (node (ref "U10") (pin "6") (pinfunction "IN1_6") (pintype "bidirectional"))
      (node (ref "U6") (pin "12") (pinfunction "PWM6_12") (pintype "output"))
    )
    (net (code "28") (name "MOT8") (class "Default")
      (node (ref "U10") (pin "5") (pinfunction "IN2_5") (pintype "bidirectional"))
      (node (ref "U6") (pin "13") (pinfunction "PWM7_13") (pintype "output"))
    )
    (net (code "29") (name "Net-(JP4-Pad4)") (class "Default")
      (node (ref "JP4") (pin "4") (pinfunction "4_4") (pintype "passive"))
      (node (ref "R11") (pin "1") (pinfunction "1_1") (pintype "passive"))
    )
    (net (code "30") (name "Net-(JP4-Pad8)") (class "Default")
      (node (ref "JP4") (pin "8") (pinfunction "8_8") (pintype "passive"))
      (node (ref "R10") (pin "1") (pinfunction "1_1") (pintype "passive"))
    )
    (net (code "31") (name "Net-(JP4-Pad12)") (class "Default")
      (node (ref "JP4") (pin "12") (pinfunction "12_12") (pintype "passive"))
      (node (ref "R9") (pin "1") (pinfunction "1_1") (pintype "passive"))
    )
    (net (code "32") (name "Net-(JP4-Pad16)") (class "Default")
      (node (ref "JP4") (pin "16") (pinfunction "16_16") (pintype "passive"))
      (node (ref "R8") (pin "1") (pinfunction "1_1") (pintype "passive"))
    )
    (net (code "33") (name "Net-(LED1-PadA)") (class "Default")
      (node (ref "LED1") (pin "A") (pinfunction "A_A") (pintype "passive"))
      (node (ref "R22") (pin "1") (pinfunction "1_1") (pintype "passive"))
    )
    (net (code "34") (name "Net-(LED2-PadA)") (class "Default")
      (node (ref "LED2") (pin "A") (pinfunction "A_A") (pintype "passive"))
      (node (ref "R23") (pin "1") (pinfunction "1_1") (pintype "passive"))
    )
    (net (code "35") (name "Net-(LED3-PadA)") (class "Default")
      (node (ref "LED3") (pin "A") (pinfunction "A_A") (pintype "passive"))
      (node (ref "R24") (pin "1") (pinfunction "1_1") (pintype "passive"))
    )
    (net (code "36") (name "Net-(Q1-G)") (class "Default")
      (node (ref "Q1") (pin "1") (pinfunction "G_1") (pintype "passive"))
      (node (ref "Q2") (pin "3") (pinfunction "C_3") (pintype "passive"))
      (node (ref "R33") (pin "1") (pinfunction "1_1") (pintype "passive"))
    )
    (net (code "37") (name "Net-(Q2-B)") (class "Default")
      (node (ref "Q2") (pin "1") (pinfunction "B_1") (pintype "passive"))
      (node (ref "R32") (pin "2") (pinfunction "2_2") (pintype "passive"))
    )
    (net (code "38") (name "Net-(R4A-2)") (class "Default")
      (node (ref "JP3") (pin "8") (pinfunction "8_8") (pintype "passive"))
      (node (ref "R4") (pin "8") (pinfunction "2_8") (pintype "passive"))
    )
    (net (code "39") (name "Net-(R4B-2)") (class "Default")
      (node (ref "JP3") (pin "7") (pinfunction "7_7") (pintype "passive"))
      (node (ref "R4") (pin "7") (pinfunction "2_7") (pintype "passive"))
    )
    (net (code "40") (name "Net-(R4C-2)") (class "Default")
      (node (ref "JP3") (pin "5") (pinfunction "5_5") (pintype "passive"))
      (node (ref "R4") (pin "5") (pinfunction "2_5") (pintype "passive"))
    )
    (net (code "41") (name "Net-(R4D-2)") (class "Default")
      (node (ref "JP3") (pin "6") (pinfunction "6_6") (pintype "passive"))
      (node (ref "R4") (pin "6") (pinfunction "2_6") (pintype "passive"))
    )
    (net (code "42") (name "Net-(R5A-2)") (class "Default")
      (node (ref "JP3") (pin "12") (pinfunction "12_12") (pintype "passive"))
      (node (ref "R5") (pin "8") (pinfunction "2_8") (pintype "passive"))
    )
    (net (code "43") (name "Net-(R5B-2)") (class "Default")
      (node (ref "JP3") (pin "11") (pinfunction "11_11") (pintype "passive"))
      (node (ref "R5") (pin "7") (pinfunction "2_7") (pintype "passive"))
    )
    (net (code "44") (name "Net-(R5C-2)") (class "Default")
      (node (ref "JP3") (pin "9") (pinfunction "9_9") (pintype "passive"))
      (node (ref "R5") (pin "5") (pinfunction "2_5") (pintype "passive"))
    )
    (net (code "45") (name "Net-(R5D-2)") (class "Default")
      (node (ref "JP3") (pin "10") (pinfunction "10_10") (pintype "passive"))
      (node (ref "R5") (pin "6") (pinfunction "2_6") (pintype "passive"))
    )
    (net (code "46") (name "Net-(R6A-2)") (class "Default")
      (node (ref "JP3") (pin "4") (pinfunction "4_4") (pintype "passive"))
      (node (ref "R6") (pin "8") (pinfunction "2_8") (pintype "passive"))
    )
    (net (code "47") (name "Net-(R6B-2)") (class "Default")
      (node (ref "JP3") (pin "3") (pinfunction "3_3") (pintype "passive"))
      (node (ref "R6") (pin "7") (pinfunction "2_7") (pintype "passive"))
    )
    (net (code "48") (name "Net-(R6C-2)") (class "Default")
      (node (ref "JP3") (pin "1") (pinfunction "1_1") (pintype "passive"))
      (node (ref "R6") (pin "5") (pinfunction "2_5") (pintype "passive"))
    )
    (net (code "49") (name "Net-(R6D-2)") (class "Default")
      (node (ref "JP3") (pin "2") (pinfunction "2_2") (pintype "passive"))
      (node (ref "R6") (pin "6") (pinfunction "2_6") (pintype "passive"))
    )
    (net (code "50") (name "Net-(R7A-2)") (class "Default")
      (node (ref "JP3") (pin "16") (pinfunction "16_16") (pintype "passive"))
      (node (ref "R7") (pin "8") (pinfunction "2_8") (pintype "passive"))
    )
    (net (code "51") (name "Net-(R7B-2)") (class "Default")
      (node (ref "JP3") (pin "15") (pinfunction "15_15") (pintype "passive"))
      (node (ref "R7") (pin "7") (pinfunction "2_7") (pintype "passive"))
    )
    (net (code "52") (name "Net-(R7C-2)") (class "Default")
      (node (ref "JP3") (pin "13") (pinfunction "13_13") (pintype "passive"))
      (node (ref "R7") (pin "5") (pinfunction "2_5") (pintype "passive"))
    )
    (net (code "53") (name "Net-(R7D-2)") (class "Default")
      (node (ref "JP3") (pin "14") (pinfunction "14_14") (pintype "passive"))
      (node (ref "R7") (pin "6") (pinfunction "2_6") (pintype "passive"))
    )
    (net (code "54") (name "Net-(R8B-1)") (class "Default")
      (node (ref "JP4") (pin "15") (pinfunction "15_15") (pintype "passive"))
      (node (ref "R8") (pin "2") (pinfunction "1_2") (pintype "passive"))
    )
    (net (code "55") (name "Net-(R8C-1)") (class "Default")
      (node (ref "JP4") (pin "13") (pinfunction "13_13") (pintype "passive"))
      (node (ref "R8") (pin "4") (pinfunction "1_4") (pintype "passive"))
    )
    (net (code "56") (name "Net-(R8D-1)") (class "Default")
      (node (ref "JP4") (pin "14") (pinfunction "14_14") (pintype "passive"))
      (node (ref "R8") (pin "3") (pinfunction "1_3") (pintype "passive"))
    )
    (net (code "57") (name "Net-(R9B-1)") (class "Default")
      (node (ref "JP4") (pin "11") (pinfunction "11_11") (pintype "passive"))
      (node (ref "R9") (pin "2") (pinfunction "1_2") (pintype "passive"))
    )
    (net (code "58") (name "Net-(R9C-1)") (class "Default")
      (node (ref "JP4") (pin "9") (pinfunction "9_9") (pintype "passive"))
      (node (ref "R9") (pin "4") (pinfunction "1_4") (pintype "passive"))
    )
    (net (code "59") (name "Net-(R9D-1)") (class "Default")
      (node (ref "JP4") (pin "10") (pinfunction "10_10") (pintype "passive"))
      (node (ref "R9") (pin "3") (pinfunction "1_3") (pintype "passive"))
    )
    (net (code "60") (name "Net-(R10B-1)") (class "Default")
      (node (ref "JP4") (pin "7") (pinfunction "7_7") (pintype "passive"))
      (node (ref "R10") (pin "2") (pinfunction "1_2") (pintype "passive"))
    )
    (net (code "61") (name "Net-(R10C-1)") (class "Default")
      (node (ref "JP4") (pin "5") (pinfunction "5_5") (pintype "passive"))
      (node (ref "R10") (pin "4") (pinfunction "1_4") (pintype "passive"))
    )
    (net (code "62") (name "Net-(R10D-1)") (class "Default")
      (node (ref "JP4") (pin "6") (pinfunction "6_6") (pintype "passive"))
      (node (ref "R10") (pin "3") (pinfunction "1_3") (pintype "passive"))
    )
    (net (code "63") (name "Net-(R11B-1)") (class "Default")
      (node (ref "JP4") (pin "3") (pinfunction "3_3") (pintype "passive"))
      (node (ref "R11") (pin "2") (pinfunction "1_2") (pintype "passive"))
    )
    (net (code "64") (name "Net-(R11C-1)") (class "Default")
      (node (ref "JP4") (pin "1") (pinfunction "1_1") (pintype "passive"))
      (node (ref "R11") (pin "4") (pinfunction "1_4") (pintype "passive"))
    )
    (net (code "65") (name "Net-(R11D-1)") (class "Default")
      (node (ref "JP4") (pin "2") (pinfunction "2_2") (pintype "passive"))
      (node (ref "R11") (pin "3") (pinfunction "1_3") (pintype "passive"))
    )
    (net (code "66") (name "Net-(U1-#OE)") (class "Default")
      (node (ref "R2") (pin "2") (pinfunction "2_2") (pintype "passive"))
      (node (ref "U1") (pin "23") (pinfunction "#OE_23") (pintype "input"))
    )
    (net (code "67") (name "Net-(U2-#OE)") (class "Default")
      (node (ref "R1") (pin "2") (pinfunction "2_2") (pintype "passive"))
      (node (ref "U2") (pin "23") (pinfunction "#OE_23") (pintype "input"))
    )
    (net (code "68") (name "Net-(U4-CAP)") (class "Default")
      (node (ref "C10") (pin "1") (pinfunction "1_1") (pintype "passive"))
      (node (ref "U4") (pin "9") (pinfunction "CAP_9") (pintype "bidirectional"))
    )
    (net (code "69") (name "Net-(U5-EN)") (class "Default")
      (node (ref "R21") (pin "1") (pinfunction "1_1") (pintype "passive"))
      (node (ref "U5") (pin "8") (pinfunction "EN_8") (pintype "bidirectional"))
    )
    (net (code "70") (name "Net-(U6-#OE)") (class "Default")
      (node (ref "R30") (pin "2") (pinfunction "2_2") (pintype "passive"))
      (node (ref "U6") (pin "23") (pinfunction "#OE_23") (pintype "input"))
    )
    (net (code "71") (name "Net-(U7-OUT1)") (class "Default")
      (node (ref "JP7") (pin "1") (pinfunction "1_1") (pintype "passive"))
      (node (ref "U7") (pin "2") (pinfunction "OUT1_2") (pintype "bidirectional"))
    )
    (net (code "72") (name "Net-(U7-OUT2)") (class "Default")
      (node (ref "JP7") (pin "2") (pinfunction "2_2") (pintype "passive"))
      (node (ref "U7") (pin "3") (pinfunction "OUT2_3") (pintype "bidirectional"))
    )
    (net (code "73") (name "Net-(U8-OUT1)") (class "Default")
      (node (ref "JP8") (pin "1") (pinfunction "1_1") (pintype "passive"))
      (node (ref "U8") (pin "2") (pinfunction "OUT1_2") (pintype "bidirectional"))
    )
    (net (code "74") (name "Net-(U8-OUT2)") (class "Default")
      (node (ref "JP8") (pin "2") (pinfunction "2_2") (pintype "passive"))
      (node (ref "U8") (pin "3") (pinfunction "OUT2_3") (pintype "bidirectional"))
    )
    (net (code "75") (name "Net-(U9-OUT1)") (class "Default")
      (node (ref "JP9") (pin "1") (pinfunction "1_1") (pintype "passive"))
      (node (ref "U9") (pin "2") (pinfunction "OUT1_2") (pintype "bidirectional"))
    )
    (net (code "76") (name "Net-(U9-OUT2)") (class "Default")
      (node (ref "JP9") (pin "2") (pinfunction "2_2") (pintype "passive"))
      (node (ref "U9") (pin "3") (pinfunction "OUT2_3") (pintype "bidirectional"))
    )
    (net (code "77") (name "Net-(U10-OUT1)") (class "Default")
      (node (ref "JP10") (pin "1") (pinfunction "1_1") (pintype "passive"))
      (node (ref "U10") (pin "2") (pinfunction "OUT1_2") (pintype "bidirectional"))
    )
    (net (code "78") (name "Net-(U10-OUT2)") (class "Default")
      (node (ref "JP10") (pin "2") (pinfunction "2_2") (pintype "passive"))
      (node (ref "U10") (pin "3") (pinfunction "OUT2_3") (pintype "bidirectional"))
    )
    (net (code "79") (name "PWR") (class "Default")
      (node (ref "R29") (pin "2") (pinfunction "2_2") (pintype "passive"))
      (node (ref "S1") (pin "1") (pinfunction "1_1") (pintype "passive"))
    )
    (net (code "80") (name "S01") (class "Default")
      (node (ref "R7") (pin "4") (pinfunction "1_4") (pintype "passive"))
      (node (ref "U2") (pin "6") (pinfunction "PWM0_6") (pintype "output"))
    )
    (net (code "81") (name "S02") (class "Default")
      (node (ref "R7") (pin "3") (pinfunction "1_3") (pintype "passive"))
      (node (ref "U2") (pin "7") (pinfunction "PWM1_7") (pintype "output"))
    )
    (net (code "82") (name "S03") (class "Default")
      (node (ref "R7") (pin "2") (pinfunction "1_2") (pintype "passive"))
      (node (ref "U2") (pin "8") (pinfunction "PWM2_8") (pintype "output"))
    )
    (net (code "83") (name "S04") (class "Default")
      (node (ref "R7") (pin "1") (pinfunction "1_1") (pintype "passive"))
      (node (ref "U2") (pin "9") (pinfunction "PWM3_9") (pintype "output"))
    )
    (net (code "84") (name "S05") (class "Default")
      (node (ref "R5") (pin "1") (pinfunction "1_1") (pintype "passive"))
      (node (ref "U2") (pin "10") (pinfunction "PWM4_10") (pintype "output"))
    )
    (net (code "85") (name "S06") (class "Default")
      (node (ref "R5") (pin "2") (pinfunction "1_2") (pintype "passive"))
      (node (ref "U2") (pin "11") (pinfunction "PWM5_11") (pintype "output"))
    )
    (net (code "86") (name "S07") (class "Default")
      (node (ref "R5") (pin "3") (pinfunction "1_3") (pintype "passive"))
      (node (ref "U2") (pin "12") (pinfunction "PWM6_12") (pintype "output"))
    )
    (net (code "87") (name "S08") (class "Default")
      (node (ref "R5") (pin "4") (pinfunction "1_4") (pintype "passive"))
      (node (ref "U2") (pin "13") (pinfunction "PWM7_13") (pintype "output"))
    )
    (net (code "88") (name "S09") (class "Default")
      (node (ref "R4") (pin "1") (pinfunction "1_1") (pintype "passive"))
      (node (ref "U2") (pin "15") (pinfunction "PWM8_15") (pintype "output"))
    )
    (net (code "89") (name "S10") (class "Default")
      (node (ref "R4") (pin "2") (pinfunction "1_2") (pintype "passive"))
      (node (ref "U2") (pin "16") (pinfunction "PWM9_16") (pintype "output"))
    )
    (net (code "90") (name "S11") (class "Default")
      (node (ref "R4") (pin "3") (pinfunction "1_3") (pintype "passive"))
      (node (ref "U2") (pin "17") (pinfunction "PWM10_17") (pintype "output"))
    )
    (net (code "91") (name "S12") (class "Default")
      (node (ref "R4") (pin "4") (pinfunction "1_4") (pintype "passive"))
      (node (ref "U2") (pin "18") (pinfunction "PWM11_18") (pintype "output"))
    )
    (net (code "92") (name "S13") (class "Default")
      (node (ref "R6") (pin "1") (pinfunction "1_1") (pintype "passive"))
      (node (ref "U2") (pin "19") (pinfunction "PWM12_19") (pintype "output"))
    )
    (net (code "93") (name "S14") (class "Default")
      (node (ref "R6") (pin "2") (pinfunction "1_2") (pintype "passive"))
      (node (ref "U2") (pin "20") (pinfunction "PWM13_20") (pintype "output"))
    )
    (net (code "94") (name "S15") (class "Default")
      (node (ref "R6") (pin "3") (pinfunction "1_3") (pintype "passive"))
      (node (ref "U2") (pin "21") (pinfunction "PWM14_21") (pintype "output"))
    )
    (net (code "95") (name "S16") (class "Default")
      (node (ref "R6") (pin "4") (pinfunction "1_4") (pintype "passive"))
      (node (ref "U2") (pin "22") (pinfunction "PWM15_22") (pintype "output"))
    )
    (net (code "96") (name "S17") (class "Default")
      (node (ref "R8") (pin "8") (pinfunction "2_8") (pintype "passive"))
      (node (ref "U1") (pin "6") (pinfunction "PWM0_6") (pintype "output"))
    )
    (net (code "97") (name "S18") (class "Default")
      (node (ref "R8") (pin "7") (pinfunction "2_7") (pintype "passive"))
      (node (ref "U1") (pin "7") (pinfunction "PWM1_7") (pintype "output"))
    )
    (net (code "98") (name "S19") (class "Default")
      (node (ref "R8") (pin "6") (pinfunction "2_6") (pintype "passive"))
      (node (ref "U1") (pin "8") (pinfunction "PWM2_8") (pintype "output"))
    )
    (net (code "99") (name "S20") (class "Default")
      (node (ref "R8") (pin "5") (pinfunction "2_5") (pintype "passive"))
      (node (ref "U1") (pin "9") (pinfunction "PWM3_9") (pintype "output"))
    )
    (net (code "100") (name "S21") (class "Default")
      (node (ref "R9") (pin "8") (pinfunction "2_8") (pintype "passive"))
      (node (ref "U1") (pin "10") (pinfunction "PWM4_10") (pintype "output"))
    )
    (net (code "101") (name "S22") (class "Default")
      (node (ref "R9") (pin "7") (pinfunction "2_7") (pintype "passive"))
      (node (ref "U1") (pin "11") (pinfunction "PWM5_11") (pintype "output"))
    )
    (net (code "102") (name "S23") (class "Default")
      (node (ref "R9") (pin "6") (pinfunction "2_6") (pintype "passive"))
      (node (ref "U1") (pin "12") (pinfunction "PWM6_12") (pintype "output"))
    )
    (net (code "103") (name "S24") (class "Default")
      (node (ref "R9") (pin "5") (pinfunction "2_5") (pintype "passive"))
      (node (ref "U1") (pin "13") (pinfunction "PWM7_13") (pintype "output"))
    )
    (net (code "104") (name "S25") (class "Default")
      (node (ref "R10") (pin "8") (pinfunction "2_8") (pintype "passive"))
      (node (ref "U1") (pin "15") (pinfunction "PWM8_15") (pintype "output"))
    )
    (net (code "105") (name "S26") (class "Default")
      (node (ref "R10") (pin "7") (pinfunction "2_7") (pintype "passive"))
      (node (ref "U1") (pin "16") (pinfunction "PWM9_16") (pintype "output"))
    )
    (net (code "106") (name "S27") (class "Default")
      (node (ref "R10") (pin "6") (pinfunction "2_6") (pintype "passive"))
      (node (ref "U1") (pin "17") (pinfunction "PWM10_17") (pintype "output"))
    )
    (net (code "107") (name "S28") (class "Default")
      (node (ref "R10") (pin "5") (pinfunction "2_5") (pintype "passive"))
      (node (ref "U1") (pin "18") (pinfunction "PWM11_18") (pintype "output"))
    )
    (net (code "108") (name "S29") (class "Default")
      (node (ref "R11") (pin "8") (pinfunction "2_8") (pintype "passive"))
      (node (ref "U1") (pin "19") (pinfunction "PWM12_19") (pintype "output"))
    )
    (net (code "109") (name "S30") (class "Default")
      (node (ref "R11") (pin "7") (pinfunction "2_7") (pintype "passive"))
      (node (ref "U1") (pin "20") (pinfunction "PWM13_20") (pintype "output"))
    )
    (net (code "110") (name "S31") (class "Default")
      (node (ref "R11") (pin "6") (pinfunction "2_6") (pintype "passive"))
      (node (ref "U1") (pin "21") (pinfunction "PWM14_21") (pintype "output"))
    )
    (net (code "111") (name "S32") (class "Default")
      (node (ref "R11") (pin "5") (pinfunction "2_5") (pintype "passive"))
      (node (ref "U1") (pin "22") (pinfunction "PWM15_22") (pintype "output"))
    )
    (net (code "112") (name "SCL") (class "Default")
      (node (ref "JP11") (pin "4") (pinfunction "4_4") (pintype "passive"))
      (node (ref "R12") (pin "2") (pinfunction "2_2") (pintype "passive"))
      (node (ref "U1") (pin "26") (pinfunction "SCL_26") (pintype "bidirectional"))
      (node (ref "U2") (pin "26") (pinfunction "SCL_26") (pintype "bidirectional"))
      (node (ref "U5") (pin "6") (pinfunction "SCL2_6") (pintype "bidirectional"))
      (node (ref "U6") (pin "26") (pinfunction "SCL_26") (pintype "bidirectional"))
    )
    (net (code "113") (name "SCL33") (class "Default")
      (node (ref "U4") (pin "19") (pinfunction "SCL/RX_19") (pintype "bidirectional"))
      (node (ref "U5") (pin "2") (pinfunction "SCL1_2") (pintype "bidirectional"))
    )
    (net (code "114") (name "SDA") (class "Default")
      (node (ref "JP11") (pin "3") (pinfunction "3_3") (pintype "passive"))
      (node (ref "R13") (pin "2") (pinfunction "2_2") (pintype "passive"))
      (node (ref "U1") (pin "27") (pinfunction "SDA_27") (pintype "bidirectional"))
      (node (ref "U2") (pin "27") (pinfunction "SDA_27") (pintype "bidirectional"))
      (node (ref "U5") (pin "5") (pinfunction "SDA2_5") (pintype "bidirectional"))
      (node (ref "U6") (pin "27") (pinfunction "SDA_27") (pintype "bidirectional"))
    )
    (net (code "115") (name "SDA33") (class "Default")
      (node (ref "U4") (pin "20") (pinfunction "SDA/TX_20") (pintype "bidirectional"))
      (node (ref "U5") (pin "3") (pinfunction "SDA1_3") (pintype "bidirectional"))
    )
    (net (code "116") (name "TERM") (class "Default")
      (node (ref "R12") (pin "1") (pinfunction "1_1") (pintype "passive"))
      (node (ref "R13") (pin "1") (pinfunction "1_1") (pintype "passive"))
      (node (ref "SW1") (pin "4") (pinfunction "4_4") (pintype "passive"))
    )
    (net (code "117") (name "VCC") (class "Default")
      (node (ref "C1") (pin "1") (pinfunction "1_1") (pintype "passive"))
      (node (ref "C15") (pin "1") (pinfunction "1_1") (pintype "passive"))
      (node (ref "C2") (pin "1") (pinfunction "1_1") (pintype "passive"))
      (node (ref "C25") (pin "1") (pinfunction "1_1") (pintype "passive"))
      (node (ref "C6") (pin "1") (pinfunction "1_1") (pintype "passive"))
      (node (ref "C7") (pin "1") (pinfunction "1_1") (pintype "passive"))
      (node (ref "JP11") (pin "2") (pinfunction "2_2") (pintype "passive"))
      (node (ref "Q1") (pin "2") (pinfunction "S_2") (pintype "passive"))
      (node (ref "R14") (pin "1") (pinfunction "1_1") (pintype "passive"))
      (node (ref "R21") (pin "2") (pinfunction "2_2") (pintype "passive"))
      (node (ref "R22") (pin "2") (pinfunction "2_2") (pintype "passive"))
      (node (ref "R33") (pin "2") (pinfunction "2_2") (pintype "passive"))
      (node (ref "S1") (pin "3") (pinfunction "2_3") (pintype "passive"))
      (node (ref "SW1") (pin "10") (pinfunction "10_10") (pintype "passive"))
      (node (ref "SW1") (pin "11") (pinfunction "11_11") (pintype "passive"))
      (node (ref "SW1") (pin "12") (pinfunction "12_12") (pintype "passive"))
      (node (ref "SW1") (pin "13") (pinfunction "13_13") (pintype "passive"))
      (node (ref "SW1") (pin "15") (pinfunction "15_15") (pintype "passive"))
      (node (ref "SW1") (pin "9") (pinfunction "9_9") (pintype "passive"))
      (node (ref "U1") (pin "28") (pinfunction "VDD_28") (pintype "power_in"))
      (node (ref "U11") (pin "1") (pinfunction "INPUT_1") (pintype "input"))
      (node (ref "U2") (pin "28") (pinfunction "VDD_28") (pintype "power_in"))
      (node (ref "U5") (pin "7") (pinfunction "VREF2_7") (pintype "bidirectional"))
    )
    (net (code "118") (name "VCCIO") (class "Default")
      (node (ref "C18") (pin "2") (pinfunction "2_2") (pintype "passive"))
      (node (ref "C21") (pin "2") (pinfunction "2_2") (pintype "passive"))
      (node (ref "C22") (pin "2") (pinfunction "2_2") (pintype "passive"))
      (node (ref "C24") (pin "2") (pinfunction "2_2") (pintype "passive"))
      (node (ref "C3") (pin "+") (pinfunction "+_+") (pintype "passive"))
      (node (ref "C5") (pin "+") (pinfunction "+_+") (pintype "passive"))
      (node (ref "J1") (pin "P$1") (pinfunction "1_P$1") (pintype "passive"))
      (node (ref "JP2") (pin "1") (pinfunction "1_1") (pintype "passive"))
      (node (ref "JP2") (pin "10") (pinfunction "10_10") (pintype "passive"))
      (node (ref "JP2") (pin "11") (pinfunction "11_11") (pintype "passive"))
      (node (ref "JP2") (pin "12") (pinfunction "12_12") (pintype "passive"))
      (node (ref "JP2") (pin "13") (pinfunction "13_13") (pintype "passive"))
      (node (ref "JP2") (pin "14") (pinfunction "14_14") (pintype "passive"))
      (node (ref "JP2") (pin "15") (pinfunction "15_15") (pintype "passive"))
      (node (ref "JP2") (pin "16") (pinfunction "16_16") (pintype "passive"))
      (node (ref "JP2") (pin "2") (pinfunction "2_2") (pintype "passive"))
      (node (ref "JP2") (pin "3") (pinfunction "3_3") (pintype "passive"))
      (node (ref "JP2") (pin "4") (pinfunction "4_4") (pintype "passive"))
      (node (ref "JP2") (pin "5") (pinfunction "5_5") (pintype "passive"))
      (node (ref "JP2") (pin "6") (pinfunction "6_6") (pintype "passive"))
      (node (ref "JP2") (pin "7") (pinfunction "7_7") (pintype "passive"))
      (node (ref "JP2") (pin "8") (pinfunction "8_8") (pintype "passive"))
      (node (ref "JP2") (pin "9") (pinfunction "9_9") (pintype "passive"))
      (node (ref "JP6") (pin "1") (pinfunction "1_1") (pintype "passive"))
      (node (ref "JP6") (pin "10") (pinfunction "10_10") (pintype "passive"))
      (node (ref "JP6") (pin "11") (pinfunction "11_11") (pintype "passive"))
      (node (ref "JP6") (pin "12") (pinfunction "12_12") (pintype "passive"))
      (node (ref "JP6") (pin "13") (pinfunction "13_13") (pintype "passive"))
      (node (ref "JP6") (pin "14") (pinfunction "14_14") (pintype "passive"))
      (node (ref "JP6") (pin "15") (pinfunction "15_15") (pintype "passive"))
      (node (ref "JP6") (pin "16") (pinfunction "16_16") (pintype "passive"))
      (node (ref "JP6") (pin "2") (pinfunction "2_2") (pintype "passive"))
      (node (ref "JP6") (pin "3") (pinfunction "3_3") (pintype "passive"))
      (node (ref "JP6") (pin "4") (pinfunction "4_4") (pintype "passive"))
      (node (ref "JP6") (pin "5") (pinfunction "5_5") (pintype "passive"))
      (node (ref "JP6") (pin "6") (pinfunction "6_6") (pintype "passive"))
      (node (ref "JP6") (pin "7") (pinfunction "7_7") (pintype "passive"))
      (node (ref "JP6") (pin "8") (pinfunction "8_8") (pintype "passive"))
      (node (ref "JP6") (pin "9") (pinfunction "9_9") (pintype "passive"))
      (node (ref "Q1") (pin "3") (pinfunction "D_3") (pintype "passive"))
      (node (ref "R23") (pin "2") (pinfunction "2_2") (pintype "passive"))
      (node (ref "U10") (pin "1") (pinfunction "VMOT_1") (pintype "bidirectional"))
      (node (ref "U7") (pin "1") (pinfunction "VMOT_1") (pintype "bidirectional"))
      (node (ref "U8") (pin "1") (pinfunction "VMOT_1") (pintype "bidirectional"))
      (node (ref "U9") (pin "1") (pinfunction "VMOT_1") (pintype "bidirectional"))
    )
    (net (code "119") (name "unconnected-(U4-XIN-Pad27)") (class "Default")
      (node (ref "U4") (pin "27") (pinfunction "XIN_27") (pintype "bidirectional"))
    )
    (net (code "120") (name "unconnected-(U4-XOUT-Pad26)") (class "Default")
      (node (ref "U4") (pin "26") (pinfunction "XOUT_26") (pintype "bidirectional"))
    )
    (net (code "121") (name "~{BOOT}") (class "Default")
      (node (ref "R26") (pin "1") (pinfunction "1_1") (pintype "passive"))
      (node (ref "U4") (pin "4") (pinfunction "BOOT_4") (pintype "bidirectional"))
    )
    (net (code "122") (name "~{RST}") (class "Default")
      (node (ref "R27") (pin "1") (pinfunction "1_1") (pintype "passive"))
      (node (ref "U4") (pin "1") (pinfunction "RST_1") (pintype "bidirectional"))
    )
  )
)
